# TCAN1146_PWR_MGMT.net
KiCad netlist of a schematic drawn in Altium Designer
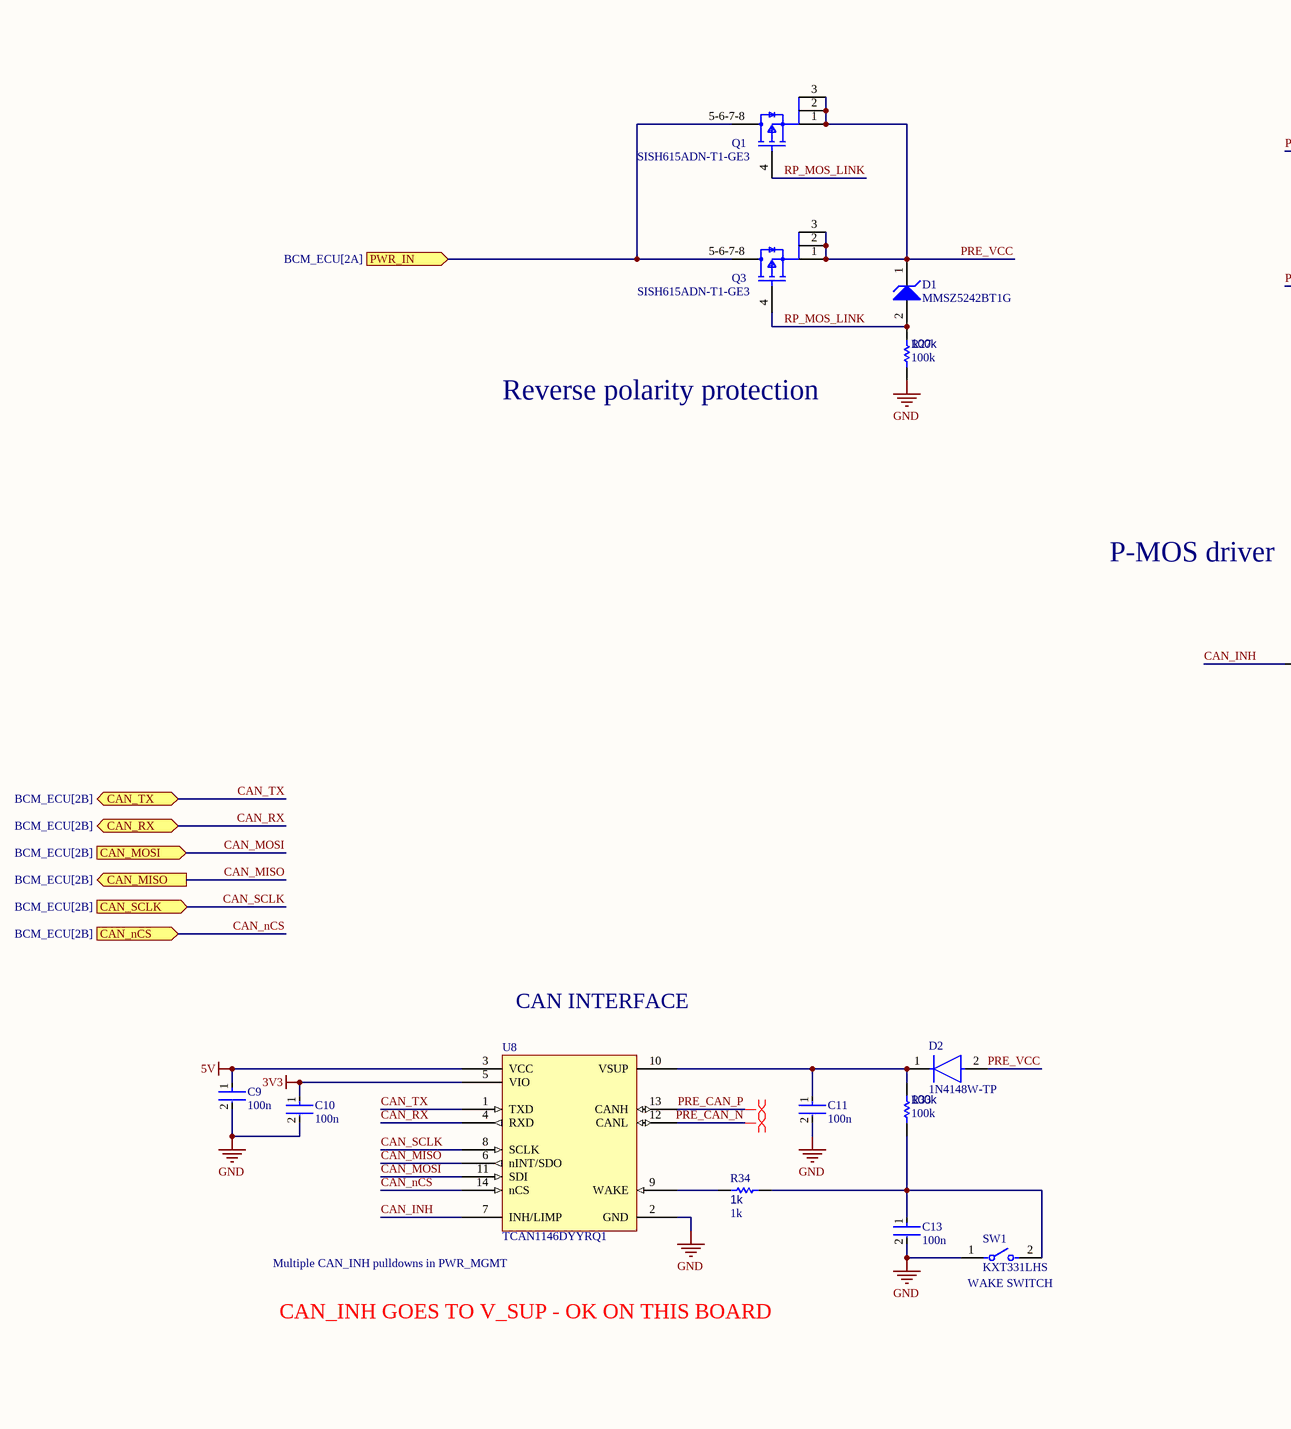
[diagram p0: TCAN1146_PWR_MGMT.SchDoc, left]
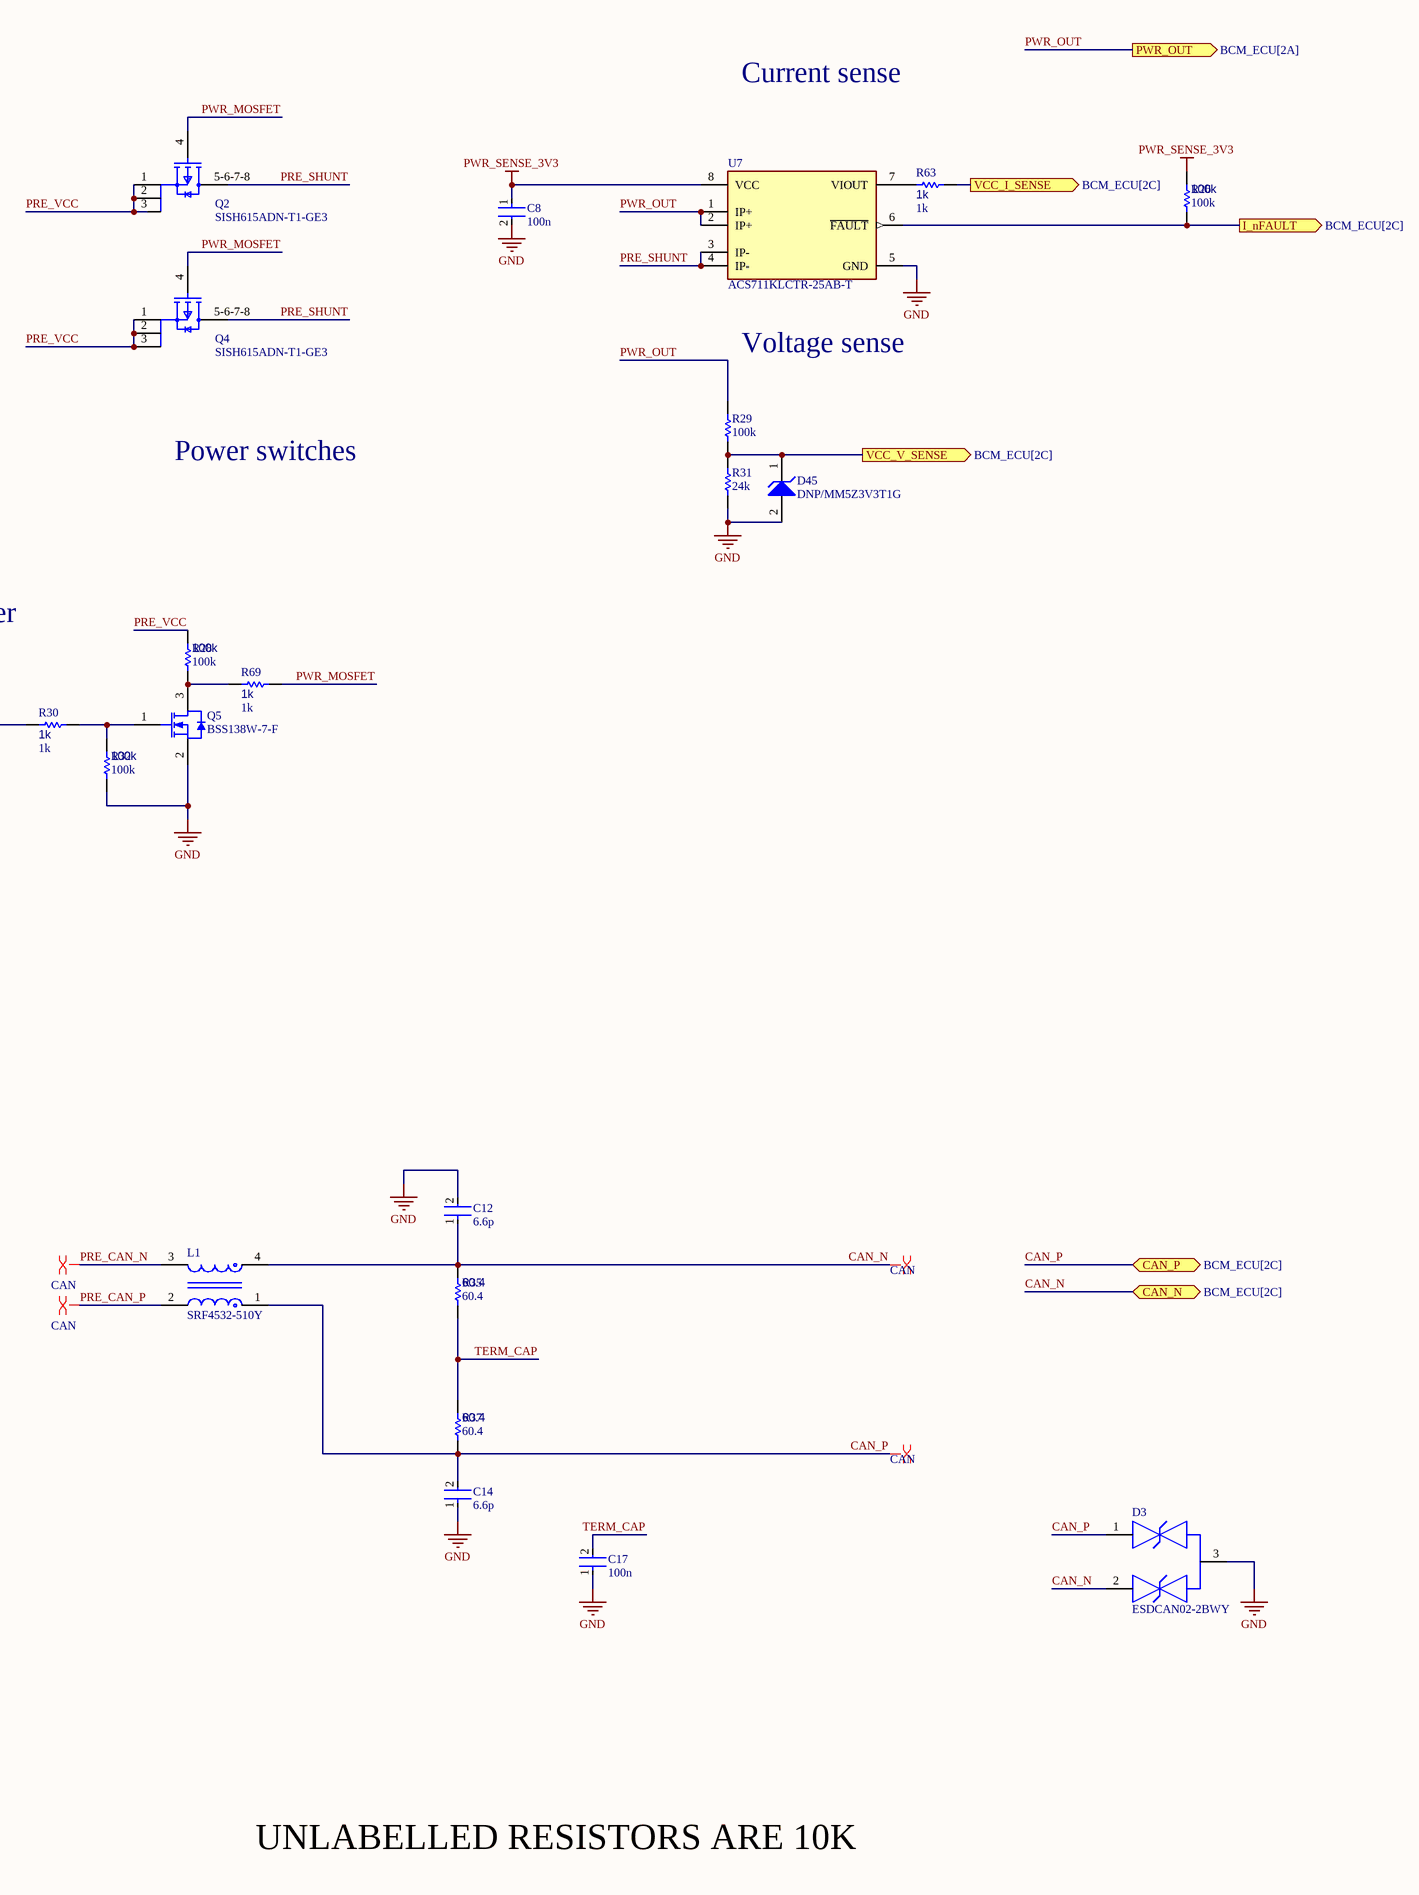
[diagram p1: TCAN1146_PWR_MGMT.SchDoc, right]

(export (version "E")
  (design (tool "Eeschema 10.0.6"))
  (components
    (comp (ref "C8")
      (value "100n")
      (footprint "FP-0402-L_1_0_0_05-W_0_5-IPC_A")
      (description "LARGE PADS, 0402 CAP, CHANGE COMMENT TO MATCH REAL P/N")
      (libsource (lib "Space Concordia") (part "b4654b650e69147ec39a6b967a45e02"))
    )
    (comp (ref "C9")
      (value "100n")
      (footprint "FP-0402-L_1_0_0_05-W_0_5-IPC_A")
      (description "LARGE PADS, 0402 CAP, CHANGE COMMENT TO MATCH REAL P/N")
      (libsource (lib "Space Concordia") (part "b4654b650e69147ec39a6b967a45e02"))
    )
    (comp (ref "C10")
      (value "100n")
      (footprint "FP-0402-L_1_0_0_05-W_0_5-IPC_A")
      (description "LARGE PADS, 0402 CAP, CHANGE COMMENT TO MATCH REAL P/N")
      (libsource (lib "Space Concordia") (part "b4654b650e69147ec39a6b967a45e02"))
    )
    (comp (ref "C11")
      (value "100n")
      (footprint "FP-0402-L_1_0_0_05-W_0_5-IPC_A")
      (description "LARGE PADS, 0402 CAP, CHANGE COMMENT TO MATCH REAL P/N")
      (libsource (lib "Space Concordia") (part "b4654b650e69147ec39a6b967a45e02"))
    )
    (comp (ref "C12")
      (value "6.6p")
      (footprint "FP-0402-L_1_0_0_05-W_0_5-IPC_A")
      (description "LARGE PADS, 0402 CAP, CHANGE COMMENT TO MATCH REAL P/N")
      (libsource (lib "Space Concordia") (part "b4654b650e69147ec39a6b967a45e02"))
    )
    (comp (ref "C13")
      (value "100n")
      (footprint "FP-0402-L_1_0_0_05-W_0_5-IPC_A")
      (description "LARGE PADS, 0402 CAP, CHANGE COMMENT TO MATCH REAL P/N")
      (libsource (lib "Space Concordia") (part "b4654b650e69147ec39a6b967a45e02"))
    )
    (comp (ref "C14")
      (value "6.6p")
      (footprint "FP-0402-L_1_0_0_05-W_0_5-IPC_A")
      (description "LARGE PADS, 0402 CAP, CHANGE COMMENT TO MATCH REAL P/N")
      (libsource (lib "Space Concordia") (part "b4654b650e69147ec39a6b967a45e02"))
    )
    (comp (ref "C17")
      (value "100n")
      (footprint "FP-0402-L_1_0_0_05-W_0_5-IPC_A")
      (description "LARGE PADS, 0402 CAP, CHANGE COMMENT TO MATCH REAL P/N")
      (libsource (lib "Space Concordia") (part "b4654b650e69147ec39a6b967a45e02"))
    )
    (comp (ref "D1")
      (value "MMSZ5242BT1G")
      (footprint "ONSC-SOD-123-2-425-04_V")
      (description "Zener Voltage Regulator, 500 mW, 2-Pin SOD-123, Pb-Free, Tape and Reel")
      (fields (field (name "MANUFACTURER") "On Semiconductor"))
      (libsource (lib "Altium Content Vault") (part "ONSC-K1A2-2"))
    )
    (comp (ref "D2")
      (value "1N4148W-TP")
      (footprint "FP-SOD-123-IPC_A")
      (description "DIODE GEN PURP 100V 150MA SOD123")
      (libsource (lib "Altium Content Vault") (part "d7152d700b627762746794eb795d46e"))
    )
    (comp (ref "D3")
      (value "ESDCAN02-2BWY")
      (footprint "FP-SOT323-3L-MFG")
      (description "TVS DIODE 26.5V 44V SOT323-3")
      (fields
        (field (name "MANUFACTURER") "STMicroelectronics")
        (field (name "OCTOPART") "https://octopart.com/esdcan02-2bwy-stmicroelectronics-58631133")
      )
      (libsource (lib "Altium Content Vault") (part "0b9019fb5e52ed66df21ec1535be59d"))
    )
    (comp (ref "D45")
      (value "DNP/MM5Z3V3T1G")
      (footprint "ONSC-SOD-523-2-502-01_V")
      (description "Zener Voltage Regulator, 500 mW, 2-Pin SOD-523, Pb-Free, Tape and Reel")
      (fields (field (name "MANUFACTURER") "On Semiconductor") (field (name "PARTNUMBER") "MM5Z3V3T1G"))
      (libsource (lib "Altium Content Vault") (part "ONSC-K1A2-2"))
    )
    (comp (ref "L1")
      (value "SRF4532-510Y")
      (footprint "FP-SRF4532-MFG")
      (description "CMC 51UH 200MA 2LN 2KOHM SMD")
      (fields (field (name "TOLERANCE") "50%"))
      (libsource (lib "Altium Content Vault") (part "aca3f6a10b859f211cca95010157f3b"))
    )
    (comp (ref "Q1")
      (value "SISH615ADN-T1-GE3")
      (footprint "SISH615ADN-T1-GE3-Footprint-1")
      (description "Trans MOSFET P-CH 20V 22.1A 8-Pin PowerPAK 1212 EP T/R")
      (libsource (lib "Space Concordia") (part "CMP-013-00036-4"))
    )
    (comp (ref "Q2")
      (value "SISH615ADN-T1-GE3")
      (footprint "SISH615ADN-T1-GE3-Footprint-1")
      (description "Trans MOSFET P-CH 20V 22.1A 8-Pin PowerPAK 1212 EP T/R")
      (libsource (lib "Space Concordia") (part "CMP-013-00036-4"))
    )
    (comp (ref "Q3")
      (value "SISH615ADN-T1-GE3")
      (footprint "SISH615ADN-T1-GE3-Footprint-1")
      (description "Trans MOSFET P-CH 20V 22.1A 8-Pin PowerPAK 1212 EP T/R")
      (libsource (lib "Space Concordia") (part "CMP-013-00036-4"))
    )
    (comp (ref "Q4")
      (value "SISH615ADN-T1-GE3")
      (footprint "SISH615ADN-T1-GE3-Footprint-1")
      (description "Trans MOSFET P-CH 20V 22.1A 8-Pin PowerPAK 1212 EP T/R")
      (libsource (lib "Space Concordia") (part "CMP-013-00036-4"))
    )
    (comp (ref "Q5")
      (value "BSS138W-7-F")
      (footprint "DIOD-SOT323-3_V")
      (fields (field (name "MANUFACTURER") "DiodesIncorporated"))
      (libsource (lib "Altium Content Vault") (part "NEMOS-GSD-3"))
    )
    (comp (ref "R26")
      (value "100k")
      (footprint "R0603B")
      (description "Resistor")
      (fields (field (name "ALTIUM_VALUE") "100k"))
      (libsource (lib "Space Concordia") (part "Resistor"))
    )
    (comp (ref "R27")
      (value "100k")
      (footprint "R0603B")
      (description "Resistor")
      (fields (field (name "ALTIUM_VALUE") "100k"))
      (libsource (lib "Space Concordia") (part "Resistor"))
    )
    (comp (ref "R28")
      (value "100k")
      (footprint "R0603B")
      (description "Resistor")
      (fields (field (name "ALTIUM_VALUE") "100k"))
      (libsource (lib "Space Concordia") (part "Resistor"))
    )
    (comp (ref "R29")
      (value "100k")
      (footprint "R0603B")
      (description "Resistor")
      (libsource (lib "Space Concordia") (part "Resistor"))
    )
    (comp (ref "R30")
      (value "1k")
      (footprint "R0603B")
      (description "Resistor")
      (fields (field (name "ALTIUM_VALUE") "1k"))
      (libsource (lib "Space Concordia") (part "Resistor"))
    )
    (comp (ref "R31")
      (value "24k")
      (footprint "R0603B")
      (description "Resistor")
      (libsource (lib "Space Concordia") (part "Resistor"))
    )
    (comp (ref "R32")
      (value "100k")
      (footprint "R0603B")
      (description "Resistor")
      (fields (field (name "ALTIUM_VALUE") "100k"))
      (libsource (lib "Space Concordia") (part "Resistor"))
    )
    (comp (ref "R33")
      (value "100k")
      (footprint "R0603B")
      (description "Resistor")
      (fields (field (name "ALTIUM_VALUE") "100k"))
      (libsource (lib "Space Concordia") (part "Resistor"))
    )
    (comp (ref "R34")
      (value "1k")
      (footprint "R0603B")
      (description "Resistor")
      (fields (field (name "ALTIUM_VALUE") "1k"))
      (libsource (lib "Space Concordia") (part "Resistor"))
    )
    (comp (ref "R35")
      (value "60.4")
      (footprint "R0603B")
      (description "Resistor")
      (fields (field (name "ALTIUM_VALUE") "60.4"))
      (libsource (lib "Space Concordia") (part "Resistor"))
    )
    (comp (ref "R37")
      (value "60.4")
      (footprint "R0603B")
      (description "Resistor")
      (fields (field (name "ALTIUM_VALUE") "60.4"))
      (libsource (lib "Space Concordia") (part "Resistor"))
    )
    (comp (ref "R63")
      (value "1k")
      (footprint "R0603B")
      (description "Resistor")
      (fields (field (name "ALTIUM_VALUE") "1k"))
      (libsource (lib "Space Concordia") (part "Resistor"))
    )
    (comp (ref "R69")
      (value "1k")
      (footprint "R0603B")
      (description "Resistor")
      (fields (field (name "ALTIUM_VALUE") "1k"))
      (libsource (lib "Space Concordia") (part "Resistor"))
    )
    (comp (ref "SW1")
      (value "KXT331LHS")
      (footprint "FP-KXT331LHS-MFG")
      (description "SWITCH TACTILE SPST-NO 0.02A 15V")
      (libsource (lib "Altium Content Vault") (part "bb27bde45df87f1f469753f287ef5ae"))
    )
    (comp (ref "U7")
      (value "ACS711KLCTR-25AB-T")
      (footprint "FP-LC-8-IPC_A")
      (description "SENSOR CURRENT HALL 25A AC/DC")
      (libsource (lib "Altium Content Vault") (part "eeba3158841281b4ae542a6e24976ab"))
    )
    (comp (ref "U8")
      (value "TCAN1146DYYRQ1")
      (footprint "TCAN1146DYYRQ1-Footprint-1")
      (libsource (lib "Space Concordia") (part "CMP-015-00012-2"))
    )
  )
  (nets
    (net (code "1") (name "/CAN_INH") (class "Default")
      (node (ref "R30") (pin "1") (pinfunction "1_1") (pintype "passive"))
      (node (ref "U8") (pin "7") (pinfunction "INH/LIMP_7") (pintype "passive"))
    )
    (net (code "2") (name "/CAN_MISO") (class "Default")
      (node (ref "U8") (pin "6") (pinfunction "nINT/SDO_6") (pintype "output"))
    )
    (net (code "3") (name "/CAN_MOSI") (class "Default")
      (node (ref "U8") (pin "11") (pinfunction "SDI_11") (pintype "input"))
    )
    (net (code "4") (name "/CAN_N") (class "Default")
      (node (ref "C12") (pin "1") (pinfunction "1_1") (pintype "passive"))
      (node (ref "D3") (pin "2") (pinfunction "2_2") (pintype "passive"))
      (node (ref "L1") (pin "4") (pinfunction "4_4") (pintype "passive"))
      (node (ref "R35") (pin "2") (pinfunction "2_2") (pintype "passive"))
    )
    (net (code "5") (name "/CAN_P") (class "Default")
      (node (ref "C14") (pin "2") (pinfunction "2_2") (pintype "passive"))
      (node (ref "D3") (pin "1") (pinfunction "1_1") (pintype "passive"))
      (node (ref "L1") (pin "1") (pinfunction "1_1") (pintype "passive"))
      (node (ref "R37") (pin "1") (pinfunction "1_1") (pintype "passive"))
    )
    (net (code "6") (name "/CAN_RX") (class "Default")
      (node (ref "U8") (pin "4") (pinfunction "RXD_4") (pintype "output"))
    )
    (net (code "7") (name "/CAN_SCLK") (class "Default")
      (node (ref "U8") (pin "8") (pinfunction "SCLK_8") (pintype "input"))
    )
    (net (code "8") (name "/CAN_TX") (class "Default")
      (node (ref "U8") (pin "1") (pinfunction "TXD_1") (pintype "input"))
    )
    (net (code "9") (name "/CAN_nCS") (class "Default")
      (node (ref "U8") (pin "14") (pinfunction "nCS_14") (pintype "input"))
    )
    (net (code "10") (name "/I_nFAULT") (class "Default")
      (node (ref "R26") (pin "1") (pinfunction "1_1") (pintype "passive"))
      (node (ref "U7") (pin "6") (pinfunction "~{FAULT}_6") (pintype "output"))
    )
    (net (code "11") (name "/PRE_CAN_N") (class "Default")
      (node (ref "L1") (pin "3") (pinfunction "3_3") (pintype "passive"))
      (node (ref "U8") (pin "12") (pinfunction "CANL_12") (pintype "bidirectional"))
    )
    (net (code "12") (name "/PRE_CAN_P") (class "Default")
      (node (ref "L1") (pin "2") (pinfunction "2_2") (pintype "passive"))
      (node (ref "U8") (pin "13") (pinfunction "CANH_13") (pintype "bidirectional"))
    )
    (net (code "13") (name "/PRE_SHUNT") (class "Default")
      (node (ref "Q2") (pin "5-6-7-8") (pinfunction "D_5-6-7-8") (pintype "passive"))
      (node (ref "Q4") (pin "5-6-7-8") (pinfunction "D_5-6-7-8") (pintype "passive"))
      (node (ref "U7") (pin "3") (pinfunction "IP-_3") (pintype "passive"))
      (node (ref "U7") (pin "4") (pinfunction "IP-_4") (pintype "passive"))
    )
    (net (code "14") (name "/PRE_VCC") (class "Default")
      (node (ref "D1") (pin "1") (pinfunction "K_1") (pintype "passive"))
      (node (ref "D2") (pin "2") (pinfunction "A_2") (pintype "passive"))
      (node (ref "Q1") (pin "1") (pinfunction "S_1") (pintype "passive"))
      (node (ref "Q1") (pin "2") (pinfunction "S_2") (pintype "passive"))
      (node (ref "Q1") (pin "3") (pinfunction "S_3") (pintype "passive"))
      (node (ref "Q2") (pin "1") (pinfunction "S_1") (pintype "passive"))
      (node (ref "Q2") (pin "2") (pinfunction "S_2") (pintype "passive"))
      (node (ref "Q2") (pin "3") (pinfunction "S_3") (pintype "passive"))
      (node (ref "Q3") (pin "1") (pinfunction "S_1") (pintype "passive"))
      (node (ref "Q3") (pin "2") (pinfunction "S_2") (pintype "passive"))
      (node (ref "Q3") (pin "3") (pinfunction "S_3") (pintype "passive"))
      (node (ref "Q4") (pin "1") (pinfunction "S_1") (pintype "passive"))
      (node (ref "Q4") (pin "2") (pinfunction "S_2") (pintype "passive"))
      (node (ref "Q4") (pin "3") (pinfunction "S_3") (pintype "passive"))
      (node (ref "R28") (pin "2") (pinfunction "2_2") (pintype "passive"))
    )
    (net (code "15") (name "/PWR_IN") (class "Default")
      (node (ref "Q1") (pin "5-6-7-8") (pinfunction "D_5-6-7-8") (pintype "passive"))
      (node (ref "Q3") (pin "5-6-7-8") (pinfunction "D_5-6-7-8") (pintype "passive"))
    )
    (net (code "16") (name "/PWR_MOSFET") (class "Default")
      (node (ref "Q2") (pin "4") (pinfunction "G_4") (pintype "passive"))
      (node (ref "Q4") (pin "4") (pinfunction "G_4") (pintype "passive"))
      (node (ref "R69") (pin "2") (pinfunction "2_2") (pintype "passive"))
    )
    (net (code "17") (name "/PWR_OUT") (class "Default")
      (node (ref "R29") (pin "2") (pinfunction "2_2") (pintype "passive"))
      (node (ref "U7") (pin "1") (pinfunction "IP+_1") (pintype "passive"))
      (node (ref "U7") (pin "2") (pinfunction "IP+_2") (pintype "passive"))
    )
    (net (code "18") (name "/RP_MOS_LINK") (class "Default")
      (node (ref "D1") (pin "2") (pinfunction "A_2") (pintype "passive"))
      (node (ref "Q1") (pin "4") (pinfunction "G_4") (pintype "passive"))
      (node (ref "Q3") (pin "4") (pinfunction "G_4") (pintype "passive"))
      (node (ref "R27") (pin "2") (pinfunction "2_2") (pintype "passive"))
    )
    (net (code "19") (name "/TERM_CAP") (class "Default")
      (node (ref "C17") (pin "2") (pinfunction "2_2") (pintype "passive"))
      (node (ref "R35") (pin "1") (pinfunction "1_1") (pintype "passive"))
      (node (ref "R37") (pin "2") (pinfunction "2_2") (pintype "passive"))
    )
    (net (code "20") (name "/VCC_I_SENSE") (class "Default")
      (node (ref "R63") (pin "1") (pinfunction "1_1") (pintype "passive"))
    )
    (net (code "21") (name "/VCC_V_SENSE") (class "Default")
      (node (ref "D45") (pin "1") (pinfunction "K_1") (pintype "passive"))
      (node (ref "R29") (pin "1") (pinfunction "1_1") (pintype "passive"))
      (node (ref "R31") (pin "2") (pinfunction "2_2") (pintype "passive"))
    )
    (net (code "22") (name "3V3") (class "Default")
      (node (ref "C10") (pin "1") (pinfunction "1_1") (pintype "passive"))
      (node (ref "U8") (pin "5") (pinfunction "VIO_5") (pintype "power_in"))
    )
    (net (code "23") (name "5V") (class "Default")
      (node (ref "C9") (pin "1") (pinfunction "1_1") (pintype "passive"))
      (node (ref "U8") (pin "3") (pinfunction "VCC_3") (pintype "power_in"))
    )
    (net (code "24") (name "GND") (class "Default")
      (node (ref "C10") (pin "2") (pinfunction "2_2") (pintype "passive"))
      (node (ref "C11") (pin "2") (pinfunction "2_2") (pintype "passive"))
      (node (ref "C12") (pin "2") (pinfunction "2_2") (pintype "passive"))
      (node (ref "C13") (pin "2") (pinfunction "2_2") (pintype "passive"))
      (node (ref "C14") (pin "1") (pinfunction "1_1") (pintype "passive"))
      (node (ref "C17") (pin "1") (pinfunction "1_1") (pintype "passive"))
      (node (ref "C8") (pin "2") (pinfunction "2_2") (pintype "passive"))
      (node (ref "C9") (pin "2") (pinfunction "2_2") (pintype "passive"))
      (node (ref "D3") (pin "3") (pinfunction "3_3") (pintype "passive"))
      (node (ref "D45") (pin "2") (pinfunction "A_2") (pintype "passive"))
      (node (ref "Q5") (pin "2") (pinfunction "S_2") (pintype "passive"))
      (node (ref "R27") (pin "1") (pinfunction "1_1") (pintype "passive"))
      (node (ref "R31") (pin "1") (pinfunction "1_1") (pintype "passive"))
      (node (ref "R32") (pin "1") (pinfunction "1_1") (pintype "passive"))
      (node (ref "SW1") (pin "1") (pinfunction "1_1") (pintype "passive"))
      (node (ref "U7") (pin "5") (pinfunction "GND_5") (pintype "power_in"))
      (node (ref "U8") (pin "2") (pinfunction "GND_2") (pintype "power_in"))
    )
    (net (code "25") (name "Net-(C13-Pad1)") (class "Default")
      (node (ref "C13") (pin "1") (pinfunction "1_1") (pintype "passive"))
      (node (ref "R33") (pin "1") (pinfunction "1_1") (pintype "passive"))
      (node (ref "R34") (pin "2") (pinfunction "2_2") (pintype "passive"))
      (node (ref "SW1") (pin "2") (pinfunction "2_2") (pintype "passive"))
    )
    (net (code "26") (name "Net-(D2-C)") (class "Default")
      (node (ref "C11") (pin "1") (pinfunction "1_1") (pintype "passive"))
      (node (ref "D2") (pin "1") (pinfunction "C_1") (pintype "passive"))
      (node (ref "R33") (pin "2") (pinfunction "2_2") (pintype "passive"))
      (node (ref "U8") (pin "10") (pinfunction "VSUP_10") (pintype "power_in"))
    )
    (net (code "27") (name "Net-(Q5-D)") (class "Default")
      (node (ref "Q5") (pin "3") (pinfunction "D_3") (pintype "passive"))
      (node (ref "R28") (pin "1") (pinfunction "1_1") (pintype "passive"))
      (node (ref "R69") (pin "1") (pinfunction "1_1") (pintype "passive"))
    )
    (net (code "28") (name "Net-(Q5-G)") (class "Default")
      (node (ref "Q5") (pin "1") (pinfunction "G_1") (pintype "passive"))
      (node (ref "R30") (pin "2") (pinfunction "2_2") (pintype "passive"))
      (node (ref "R32") (pin "2") (pinfunction "2_2") (pintype "passive"))
    )
    (net (code "29") (name "Net-(U7-VIOUT)") (class "Default")
      (node (ref "R63") (pin "2") (pinfunction "2_2") (pintype "passive"))
      (node (ref "U7") (pin "7") (pinfunction "VIOUT_7") (pintype "passive"))
    )
    (net (code "30") (name "Net-(U8-WAKE)") (class "Default")
      (node (ref "R34") (pin "1") (pinfunction "1_1") (pintype "passive"))
      (node (ref "U8") (pin "9") (pinfunction "WAKE_9") (pintype "input"))
    )
    (net (code "31") (name "PWR_SENSE_3V3") (class "Default")
      (node (ref "C8") (pin "1") (pinfunction "1_1") (pintype "passive"))
      (node (ref "R26") (pin "2") (pinfunction "2_2") (pintype "passive"))
      (node (ref "U7") (pin "8") (pinfunction "VCC_8") (pintype "power_in"))
    )
  )
)
